# backplate5V_final_rev01.net
KiCad netlist of a schematic drawn in EAGLE
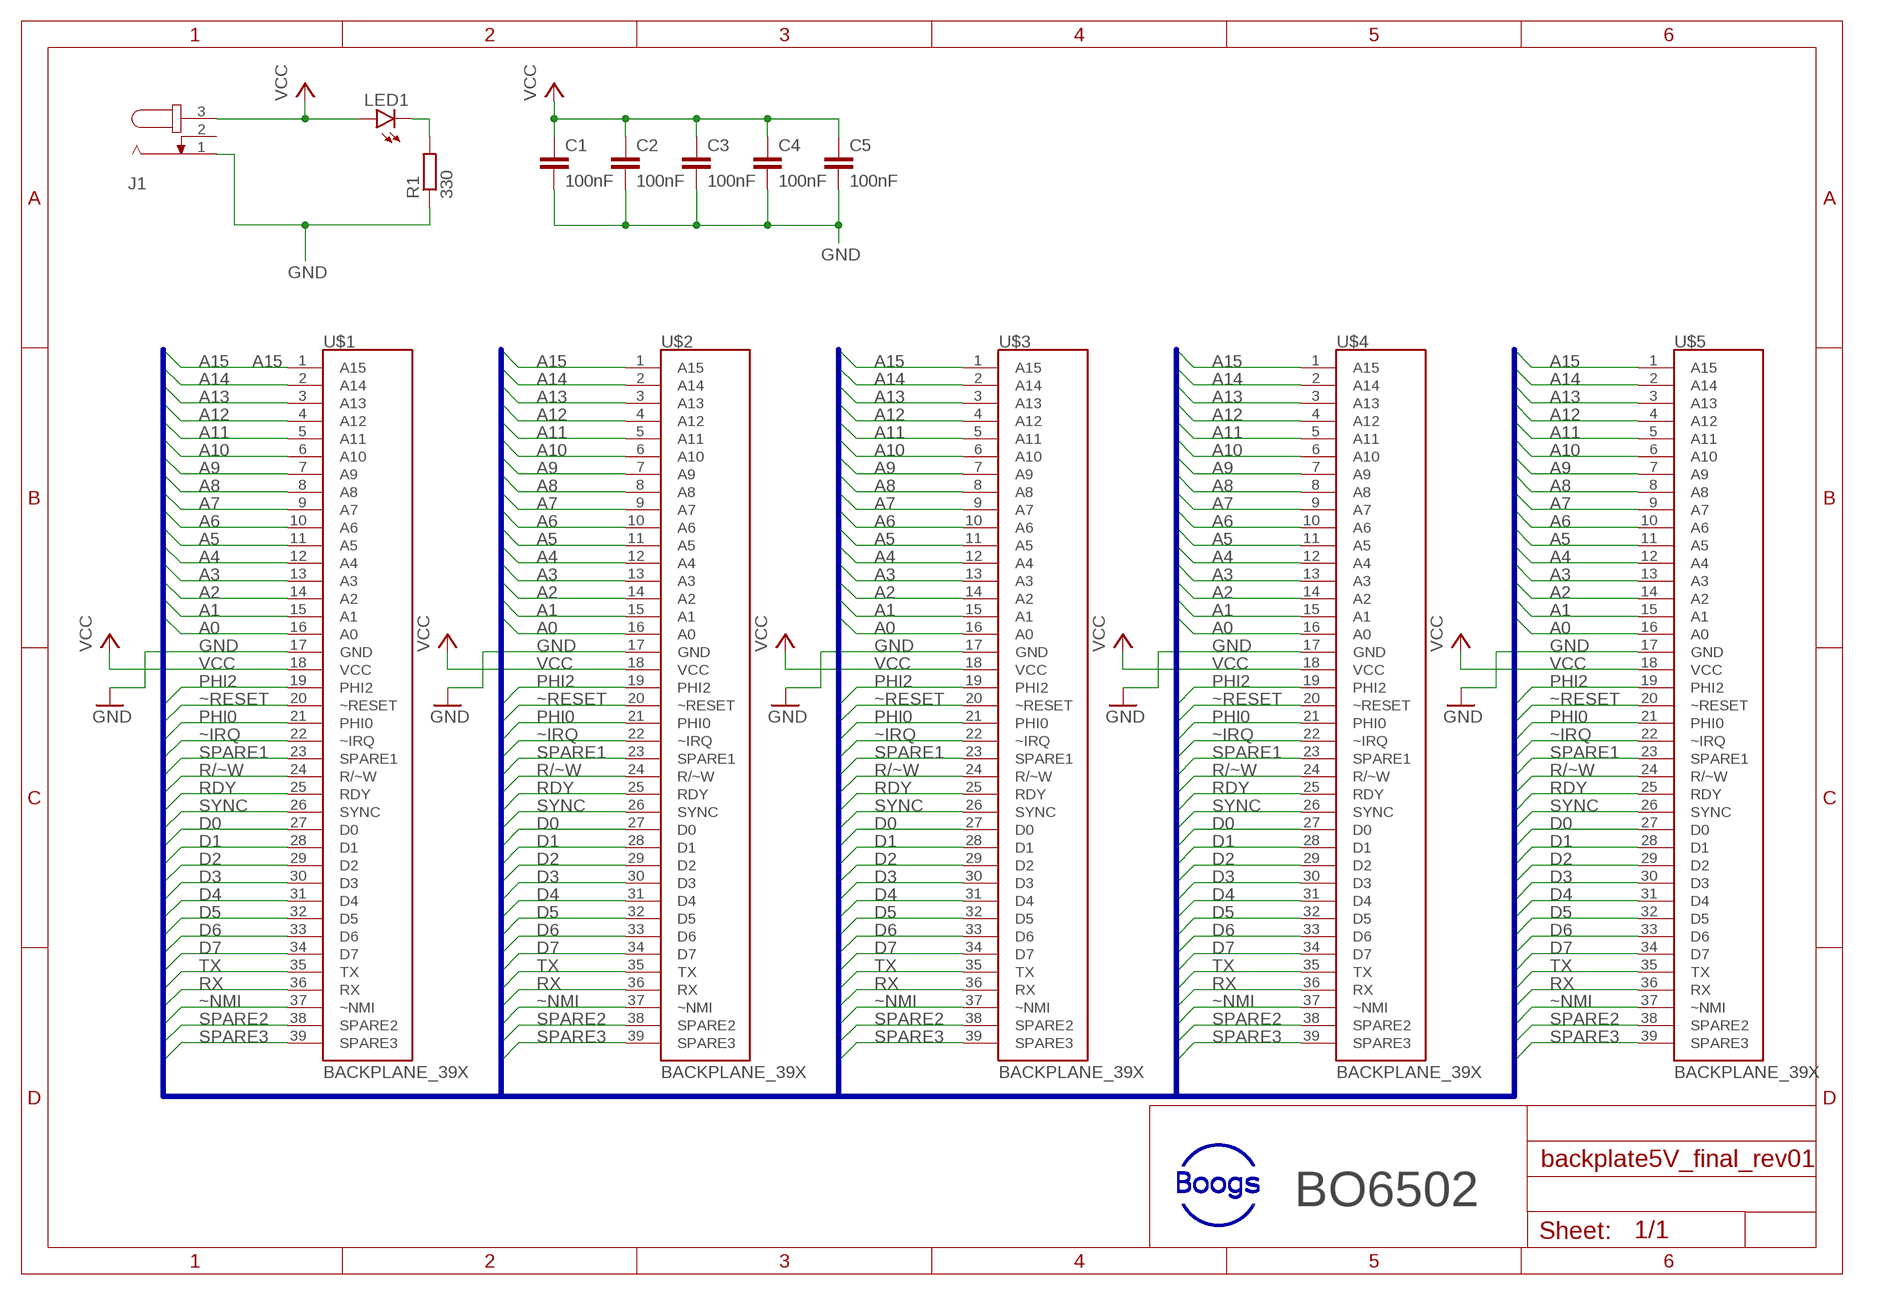
[diagram p0: schematic, sheet 1]

(export (version "E")
  (design (tool "Eeschema 10.0.6"))
  (components
    (comp (ref "C1")
      (value "100nF")
      (footprint "eagle-import:C025-025X050")
      (libsource (lib "eagle-import") (part "C-EU025-025X050"))
    )
    (comp (ref "C2")
      (value "100nF")
      (footprint "eagle-import:C025-025X050")
      (libsource (lib "eagle-import") (part "C-EU025-025X050"))
    )
    (comp (ref "C3")
      (value "100nF")
      (footprint "eagle-import:C025-025X050")
      (libsource (lib "eagle-import") (part "C-EU025-025X050"))
    )
    (comp (ref "C4")
      (value "100nF")
      (footprint "eagle-import:C025-025X050")
      (libsource (lib "eagle-import") (part "C-EU025-025X050"))
    )
    (comp (ref "C5")
      (value "100nF")
      (footprint "eagle-import:C025-025X050")
      (libsource (lib "eagle-import") (part "C-EU025-025X050"))
    )
    (comp (ref "J1")
      (value "JACK-PLUG1")
      (footprint "eagle-import:SPC4078")
      (libsource (lib "eagle-import") (part "JACK-PLUG1"))
    )
    (comp (ref "LED1")
      (value "LED5MM")
      (footprint "eagle-import:LED5MM")
      (libsource (lib "eagle-import") (part "LED5MM"))
    )
    (comp (ref "R1")
      (value "330")
      (footprint "eagle-import:0207_10")
      (libsource (lib "eagle-import") (part "R-EU_0207/10"))
    )
    (comp (ref "U$1")
      (value "BACKPLANE_39X")
      (footprint "eagle-import:BP_39X")
      (fields (field (name "A15") "A15"))
      (libsource (lib "eagle-import") (part "BACKPLANE_39X"))
    )
    (comp (ref "U$2")
      (value "BACKPLANE_39X")
      (footprint "eagle-import:BP_39X")
      (libsource (lib "eagle-import") (part "BACKPLANE_39X"))
    )
    (comp (ref "U$3")
      (value "BACKPLANE_39X")
      (footprint "eagle-import:BP_39X")
      (libsource (lib "eagle-import") (part "BACKPLANE_39X"))
    )
    (comp (ref "U$4")
      (value "BACKPLANE_39X")
      (footprint "eagle-import:BP_39X")
      (libsource (lib "eagle-import") (part "BACKPLANE_39X"))
    )
    (comp (ref "U$5")
      (value "BACKPLANE_39X")
      (footprint "eagle-import:BP_39X")
      (libsource (lib "eagle-import") (part "BACKPLANE_39X"))
    )
  )
  (nets
    (net (code "1") (name "/A0") (class "Default")
      (node (ref "U$1") (pin "16") (pinfunction "A0_16") (pintype "bidirectional"))
      (node (ref "U$2") (pin "16") (pinfunction "A0_16") (pintype "bidirectional"))
      (node (ref "U$3") (pin "16") (pinfunction "A0_16") (pintype "bidirectional"))
      (node (ref "U$4") (pin "16") (pinfunction "A0_16") (pintype "bidirectional"))
      (node (ref "U$5") (pin "16") (pinfunction "A0_16") (pintype "bidirectional"))
    )
    (net (code "2") (name "/A1") (class "Default")
      (node (ref "U$1") (pin "15") (pinfunction "A1_15") (pintype "bidirectional"))
      (node (ref "U$2") (pin "15") (pinfunction "A1_15") (pintype "bidirectional"))
      (node (ref "U$3") (pin "15") (pinfunction "A1_15") (pintype "bidirectional"))
      (node (ref "U$4") (pin "15") (pinfunction "A1_15") (pintype "bidirectional"))
      (node (ref "U$5") (pin "15") (pinfunction "A1_15") (pintype "bidirectional"))
    )
    (net (code "3") (name "/A2") (class "Default")
      (node (ref "U$1") (pin "14") (pinfunction "A2_14") (pintype "bidirectional"))
      (node (ref "U$2") (pin "14") (pinfunction "A2_14") (pintype "bidirectional"))
      (node (ref "U$3") (pin "14") (pinfunction "A2_14") (pintype "bidirectional"))
      (node (ref "U$4") (pin "14") (pinfunction "A2_14") (pintype "bidirectional"))
      (node (ref "U$5") (pin "14") (pinfunction "A2_14") (pintype "bidirectional"))
    )
    (net (code "4") (name "/A3") (class "Default")
      (node (ref "U$1") (pin "13") (pinfunction "A3_13") (pintype "bidirectional"))
      (node (ref "U$2") (pin "13") (pinfunction "A3_13") (pintype "bidirectional"))
      (node (ref "U$3") (pin "13") (pinfunction "A3_13") (pintype "bidirectional"))
      (node (ref "U$4") (pin "13") (pinfunction "A3_13") (pintype "bidirectional"))
      (node (ref "U$5") (pin "13") (pinfunction "A3_13") (pintype "bidirectional"))
    )
    (net (code "5") (name "/A4") (class "Default")
      (node (ref "U$1") (pin "12") (pinfunction "A4_12") (pintype "bidirectional"))
      (node (ref "U$2") (pin "12") (pinfunction "A4_12") (pintype "bidirectional"))
      (node (ref "U$3") (pin "12") (pinfunction "A4_12") (pintype "bidirectional"))
      (node (ref "U$4") (pin "12") (pinfunction "A4_12") (pintype "bidirectional"))
      (node (ref "U$5") (pin "12") (pinfunction "A4_12") (pintype "bidirectional"))
    )
    (net (code "6") (name "/A5") (class "Default")
      (node (ref "U$1") (pin "11") (pinfunction "A5_11") (pintype "bidirectional"))
      (node (ref "U$2") (pin "11") (pinfunction "A5_11") (pintype "bidirectional"))
      (node (ref "U$3") (pin "11") (pinfunction "A5_11") (pintype "bidirectional"))
      (node (ref "U$4") (pin "11") (pinfunction "A5_11") (pintype "bidirectional"))
      (node (ref "U$5") (pin "11") (pinfunction "A5_11") (pintype "bidirectional"))
    )
    (net (code "7") (name "/A6") (class "Default")
      (node (ref "U$1") (pin "10") (pinfunction "A6_10") (pintype "bidirectional"))
      (node (ref "U$2") (pin "10") (pinfunction "A6_10") (pintype "bidirectional"))
      (node (ref "U$3") (pin "10") (pinfunction "A6_10") (pintype "bidirectional"))
      (node (ref "U$4") (pin "10") (pinfunction "A6_10") (pintype "bidirectional"))
      (node (ref "U$5") (pin "10") (pinfunction "A6_10") (pintype "bidirectional"))
    )
    (net (code "8") (name "/A7") (class "Default")
      (node (ref "U$1") (pin "9") (pinfunction "A7_9") (pintype "bidirectional"))
      (node (ref "U$2") (pin "9") (pinfunction "A7_9") (pintype "bidirectional"))
      (node (ref "U$3") (pin "9") (pinfunction "A7_9") (pintype "bidirectional"))
      (node (ref "U$4") (pin "9") (pinfunction "A7_9") (pintype "bidirectional"))
      (node (ref "U$5") (pin "9") (pinfunction "A7_9") (pintype "bidirectional"))
    )
    (net (code "9") (name "/A8") (class "Default")
      (node (ref "U$1") (pin "8") (pinfunction "A8_8") (pintype "bidirectional"))
      (node (ref "U$2") (pin "8") (pinfunction "A8_8") (pintype "bidirectional"))
      (node (ref "U$3") (pin "8") (pinfunction "A8_8") (pintype "bidirectional"))
      (node (ref "U$4") (pin "8") (pinfunction "A8_8") (pintype "bidirectional"))
      (node (ref "U$5") (pin "8") (pinfunction "A8_8") (pintype "bidirectional"))
    )
    (net (code "10") (name "/A9") (class "Default")
      (node (ref "U$1") (pin "7") (pinfunction "A9_7") (pintype "bidirectional"))
      (node (ref "U$2") (pin "7") (pinfunction "A9_7") (pintype "bidirectional"))
      (node (ref "U$3") (pin "7") (pinfunction "A9_7") (pintype "bidirectional"))
      (node (ref "U$4") (pin "7") (pinfunction "A9_7") (pintype "bidirectional"))
      (node (ref "U$5") (pin "7") (pinfunction "A9_7") (pintype "bidirectional"))
    )
    (net (code "11") (name "/A10") (class "Default")
      (node (ref "U$1") (pin "6") (pinfunction "A10_6") (pintype "bidirectional"))
      (node (ref "U$2") (pin "6") (pinfunction "A10_6") (pintype "bidirectional"))
      (node (ref "U$3") (pin "6") (pinfunction "A10_6") (pintype "bidirectional"))
      (node (ref "U$4") (pin "6") (pinfunction "A10_6") (pintype "bidirectional"))
      (node (ref "U$5") (pin "6") (pinfunction "A10_6") (pintype "bidirectional"))
    )
    (net (code "12") (name "/A11") (class "Default")
      (node (ref "U$1") (pin "5") (pinfunction "A11_5") (pintype "bidirectional"))
      (node (ref "U$2") (pin "5") (pinfunction "A11_5") (pintype "bidirectional"))
      (node (ref "U$3") (pin "5") (pinfunction "A11_5") (pintype "bidirectional"))
      (node (ref "U$4") (pin "5") (pinfunction "A11_5") (pintype "bidirectional"))
      (node (ref "U$5") (pin "5") (pinfunction "A11_5") (pintype "bidirectional"))
    )
    (net (code "13") (name "/A12") (class "Default")
      (node (ref "U$1") (pin "4") (pinfunction "A12_4") (pintype "bidirectional"))
      (node (ref "U$2") (pin "4") (pinfunction "A12_4") (pintype "bidirectional"))
      (node (ref "U$3") (pin "4") (pinfunction "A12_4") (pintype "bidirectional"))
      (node (ref "U$4") (pin "4") (pinfunction "A12_4") (pintype "bidirectional"))
      (node (ref "U$5") (pin "4") (pinfunction "A12_4") (pintype "bidirectional"))
    )
    (net (code "14") (name "/A13") (class "Default")
      (node (ref "U$1") (pin "3") (pinfunction "A13_3") (pintype "bidirectional"))
      (node (ref "U$2") (pin "3") (pinfunction "A13_3") (pintype "bidirectional"))
      (node (ref "U$3") (pin "3") (pinfunction "A13_3") (pintype "bidirectional"))
      (node (ref "U$4") (pin "3") (pinfunction "A13_3") (pintype "bidirectional"))
      (node (ref "U$5") (pin "3") (pinfunction "A13_3") (pintype "bidirectional"))
    )
    (net (code "15") (name "/A14") (class "Default")
      (node (ref "U$1") (pin "2") (pinfunction "A14_2") (pintype "bidirectional"))
      (node (ref "U$2") (pin "2") (pinfunction "A14_2") (pintype "bidirectional"))
      (node (ref "U$3") (pin "2") (pinfunction "A14_2") (pintype "bidirectional"))
      (node (ref "U$4") (pin "2") (pinfunction "A14_2") (pintype "bidirectional"))
      (node (ref "U$5") (pin "2") (pinfunction "A14_2") (pintype "bidirectional"))
    )
    (net (code "16") (name "/A15") (class "Default")
      (node (ref "U$1") (pin "1") (pinfunction "A15_1") (pintype "bidirectional"))
      (node (ref "U$2") (pin "1") (pinfunction "A15_1") (pintype "bidirectional"))
      (node (ref "U$3") (pin "1") (pinfunction "A15_1") (pintype "bidirectional"))
      (node (ref "U$4") (pin "1") (pinfunction "A15_1") (pintype "bidirectional"))
      (node (ref "U$5") (pin "1") (pinfunction "A15_1") (pintype "bidirectional"))
    )
    (net (code "17") (name "/D0") (class "Default")
      (node (ref "U$1") (pin "27") (pinfunction "D0_27") (pintype "bidirectional"))
      (node (ref "U$2") (pin "27") (pinfunction "D0_27") (pintype "bidirectional"))
      (node (ref "U$3") (pin "27") (pinfunction "D0_27") (pintype "bidirectional"))
      (node (ref "U$4") (pin "27") (pinfunction "D0_27") (pintype "bidirectional"))
      (node (ref "U$5") (pin "27") (pinfunction "D0_27") (pintype "bidirectional"))
    )
    (net (code "18") (name "/D1") (class "Default")
      (node (ref "U$1") (pin "28") (pinfunction "D1_28") (pintype "bidirectional"))
      (node (ref "U$2") (pin "28") (pinfunction "D1_28") (pintype "bidirectional"))
      (node (ref "U$3") (pin "28") (pinfunction "D1_28") (pintype "bidirectional"))
      (node (ref "U$4") (pin "28") (pinfunction "D1_28") (pintype "bidirectional"))
      (node (ref "U$5") (pin "28") (pinfunction "D1_28") (pintype "bidirectional"))
    )
    (net (code "19") (name "/D2") (class "Default")
      (node (ref "U$1") (pin "29") (pinfunction "D2_29") (pintype "bidirectional"))
      (node (ref "U$2") (pin "29") (pinfunction "D2_29") (pintype "bidirectional"))
      (node (ref "U$3") (pin "29") (pinfunction "D2_29") (pintype "bidirectional"))
      (node (ref "U$4") (pin "29") (pinfunction "D2_29") (pintype "bidirectional"))
      (node (ref "U$5") (pin "29") (pinfunction "D2_29") (pintype "bidirectional"))
    )
    (net (code "20") (name "/D3") (class "Default")
      (node (ref "U$1") (pin "30") (pinfunction "D3_30") (pintype "bidirectional"))
      (node (ref "U$2") (pin "30") (pinfunction "D3_30") (pintype "bidirectional"))
      (node (ref "U$3") (pin "30") (pinfunction "D3_30") (pintype "bidirectional"))
      (node (ref "U$4") (pin "30") (pinfunction "D3_30") (pintype "bidirectional"))
      (node (ref "U$5") (pin "30") (pinfunction "D3_30") (pintype "bidirectional"))
    )
    (net (code "21") (name "/D4") (class "Default")
      (node (ref "U$1") (pin "31") (pinfunction "D4_31") (pintype "bidirectional"))
      (node (ref "U$2") (pin "31") (pinfunction "D4_31") (pintype "bidirectional"))
      (node (ref "U$3") (pin "31") (pinfunction "D4_31") (pintype "bidirectional"))
      (node (ref "U$4") (pin "31") (pinfunction "D4_31") (pintype "bidirectional"))
      (node (ref "U$5") (pin "31") (pinfunction "D4_31") (pintype "bidirectional"))
    )
    (net (code "22") (name "/D5") (class "Default")
      (node (ref "U$1") (pin "32") (pinfunction "D5_32") (pintype "bidirectional"))
      (node (ref "U$2") (pin "32") (pinfunction "D5_32") (pintype "bidirectional"))
      (node (ref "U$3") (pin "32") (pinfunction "D5_32") (pintype "bidirectional"))
      (node (ref "U$4") (pin "32") (pinfunction "D5_32") (pintype "bidirectional"))
      (node (ref "U$5") (pin "32") (pinfunction "D5_32") (pintype "bidirectional"))
    )
    (net (code "23") (name "/D6") (class "Default")
      (node (ref "U$1") (pin "33") (pinfunction "D6_33") (pintype "bidirectional"))
      (node (ref "U$2") (pin "33") (pinfunction "D6_33") (pintype "bidirectional"))
      (node (ref "U$3") (pin "33") (pinfunction "D6_33") (pintype "bidirectional"))
      (node (ref "U$4") (pin "33") (pinfunction "D6_33") (pintype "bidirectional"))
      (node (ref "U$5") (pin "33") (pinfunction "D6_33") (pintype "bidirectional"))
    )
    (net (code "24") (name "/D7") (class "Default")
      (node (ref "U$1") (pin "34") (pinfunction "D7_34") (pintype "bidirectional"))
      (node (ref "U$2") (pin "34") (pinfunction "D7_34") (pintype "bidirectional"))
      (node (ref "U$3") (pin "34") (pinfunction "D7_34") (pintype "bidirectional"))
      (node (ref "U$4") (pin "34") (pinfunction "D7_34") (pintype "bidirectional"))
      (node (ref "U$5") (pin "34") (pinfunction "D7_34") (pintype "bidirectional"))
    )
    (net (code "25") (name "/PHI0") (class "Default")
      (node (ref "U$1") (pin "21") (pinfunction "PHI0_21") (pintype "bidirectional"))
      (node (ref "U$2") (pin "21") (pinfunction "PHI0_21") (pintype "bidirectional"))
      (node (ref "U$3") (pin "21") (pinfunction "PHI0_21") (pintype "bidirectional"))
      (node (ref "U$4") (pin "21") (pinfunction "PHI0_21") (pintype "bidirectional"))
      (node (ref "U$5") (pin "21") (pinfunction "PHI0_21") (pintype "bidirectional"))
    )
    (net (code "26") (name "/PHI2") (class "Default")
      (node (ref "U$1") (pin "19") (pinfunction "PHI2_19") (pintype "bidirectional"))
      (node (ref "U$2") (pin "19") (pinfunction "PHI2_19") (pintype "bidirectional"))
      (node (ref "U$3") (pin "19") (pinfunction "PHI2_19") (pintype "bidirectional"))
      (node (ref "U$4") (pin "19") (pinfunction "PHI2_19") (pintype "bidirectional"))
      (node (ref "U$5") (pin "19") (pinfunction "PHI2_19") (pintype "bidirectional"))
    )
    (net (code "27") (name "/RDY") (class "Default")
      (node (ref "U$1") (pin "25") (pinfunction "RDY_25") (pintype "bidirectional"))
      (node (ref "U$2") (pin "25") (pinfunction "RDY_25") (pintype "bidirectional"))
      (node (ref "U$3") (pin "25") (pinfunction "RDY_25") (pintype "bidirectional"))
      (node (ref "U$4") (pin "25") (pinfunction "RDY_25") (pintype "bidirectional"))
      (node (ref "U$5") (pin "25") (pinfunction "RDY_25") (pintype "bidirectional"))
    )
    (net (code "28") (name "/RX") (class "Default")
      (node (ref "U$1") (pin "36") (pinfunction "RX_36") (pintype "bidirectional"))
      (node (ref "U$2") (pin "36") (pinfunction "RX_36") (pintype "bidirectional"))
      (node (ref "U$3") (pin "36") (pinfunction "RX_36") (pintype "bidirectional"))
      (node (ref "U$4") (pin "36") (pinfunction "RX_36") (pintype "bidirectional"))
      (node (ref "U$5") (pin "36") (pinfunction "RX_36") (pintype "bidirectional"))
    )
    (net (code "29") (name "/R{slash}~{W}") (class "Default")
      (node (ref "U$1") (pin "24") (pinfunction "R/~{W}_24") (pintype "bidirectional"))
      (node (ref "U$2") (pin "24") (pinfunction "R/~{W}_24") (pintype "bidirectional"))
      (node (ref "U$3") (pin "24") (pinfunction "R/~{W}_24") (pintype "bidirectional"))
      (node (ref "U$4") (pin "24") (pinfunction "R/~{W}_24") (pintype "bidirectional"))
      (node (ref "U$5") (pin "24") (pinfunction "R/~{W}_24") (pintype "bidirectional"))
    )
    (net (code "30") (name "/SPARE1") (class "Default")
      (node (ref "U$1") (pin "23") (pinfunction "SPARE1_23") (pintype "bidirectional"))
      (node (ref "U$2") (pin "23") (pinfunction "SPARE1_23") (pintype "bidirectional"))
      (node (ref "U$3") (pin "23") (pinfunction "SPARE1_23") (pintype "bidirectional"))
      (node (ref "U$4") (pin "23") (pinfunction "SPARE1_23") (pintype "bidirectional"))
      (node (ref "U$5") (pin "23") (pinfunction "SPARE1_23") (pintype "bidirectional"))
    )
    (net (code "31") (name "/SPARE2") (class "Default")
      (node (ref "U$1") (pin "38") (pinfunction "SPARE2_38") (pintype "bidirectional"))
      (node (ref "U$2") (pin "38") (pinfunction "SPARE2_38") (pintype "bidirectional"))
      (node (ref "U$3") (pin "38") (pinfunction "SPARE2_38") (pintype "bidirectional"))
      (node (ref "U$4") (pin "38") (pinfunction "SPARE2_38") (pintype "bidirectional"))
      (node (ref "U$5") (pin "38") (pinfunction "SPARE2_38") (pintype "bidirectional"))
    )
    (net (code "32") (name "/SPARE3") (class "Default")
      (node (ref "U$1") (pin "39") (pinfunction "SPARE3_39") (pintype "bidirectional"))
      (node (ref "U$2") (pin "39") (pinfunction "SPARE3_39") (pintype "bidirectional"))
      (node (ref "U$3") (pin "39") (pinfunction "SPARE3_39") (pintype "bidirectional"))
      (node (ref "U$4") (pin "39") (pinfunction "SPARE3_39") (pintype "bidirectional"))
      (node (ref "U$5") (pin "39") (pinfunction "SPARE3_39") (pintype "bidirectional"))
    )
    (net (code "33") (name "/SYNC") (class "Default")
      (node (ref "U$1") (pin "26") (pinfunction "SYNC_26") (pintype "bidirectional"))
      (node (ref "U$2") (pin "26") (pinfunction "SYNC_26") (pintype "bidirectional"))
      (node (ref "U$3") (pin "26") (pinfunction "SYNC_26") (pintype "bidirectional"))
      (node (ref "U$4") (pin "26") (pinfunction "SYNC_26") (pintype "bidirectional"))
      (node (ref "U$5") (pin "26") (pinfunction "SYNC_26") (pintype "bidirectional"))
    )
    (net (code "34") (name "/TX") (class "Default")
      (node (ref "U$1") (pin "35") (pinfunction "TX_35") (pintype "bidirectional"))
      (node (ref "U$2") (pin "35") (pinfunction "TX_35") (pintype "bidirectional"))
      (node (ref "U$3") (pin "35") (pinfunction "TX_35") (pintype "bidirectional"))
      (node (ref "U$4") (pin "35") (pinfunction "TX_35") (pintype "bidirectional"))
      (node (ref "U$5") (pin "35") (pinfunction "TX_35") (pintype "bidirectional"))
    )
    (net (code "35") (name "/~{IRQ}") (class "Default")
      (node (ref "U$1") (pin "22") (pinfunction "~{IRQ}_22") (pintype "bidirectional"))
      (node (ref "U$2") (pin "22") (pinfunction "~{IRQ}_22") (pintype "bidirectional"))
      (node (ref "U$3") (pin "22") (pinfunction "~{IRQ}_22") (pintype "bidirectional"))
      (node (ref "U$4") (pin "22") (pinfunction "~{IRQ}_22") (pintype "bidirectional"))
      (node (ref "U$5") (pin "22") (pinfunction "~{IRQ}_22") (pintype "bidirectional"))
    )
    (net (code "36") (name "/~{NMI}") (class "Default")
      (node (ref "U$1") (pin "37") (pinfunction "~{NMI}_37") (pintype "bidirectional"))
      (node (ref "U$2") (pin "37") (pinfunction "~{NMI}_37") (pintype "bidirectional"))
      (node (ref "U$3") (pin "37") (pinfunction "~{NMI}_37") (pintype "bidirectional"))
      (node (ref "U$4") (pin "37") (pinfunction "~{NMI}_37") (pintype "bidirectional"))
      (node (ref "U$5") (pin "37") (pinfunction "~{NMI}_37") (pintype "bidirectional"))
    )
    (net (code "37") (name "/~{RESET}") (class "Default")
      (node (ref "U$1") (pin "20") (pinfunction "~{RESET}_20") (pintype "bidirectional"))
      (node (ref "U$2") (pin "20") (pinfunction "~{RESET}_20") (pintype "bidirectional"))
      (node (ref "U$3") (pin "20") (pinfunction "~{RESET}_20") (pintype "bidirectional"))
      (node (ref "U$4") (pin "20") (pinfunction "~{RESET}_20") (pintype "bidirectional"))
      (node (ref "U$5") (pin "20") (pinfunction "~{RESET}_20") (pintype "bidirectional"))
    )
    (net (code "38") (name "GND") (class "Default")
      (node (ref "C1") (pin "2") (pinfunction "2_2") (pintype "passive"))
      (node (ref "C2") (pin "2") (pinfunction "2_2") (pintype "passive"))
      (node (ref "C3") (pin "2") (pinfunction "2_2") (pintype "passive"))
      (node (ref "C4") (pin "2") (pinfunction "2_2") (pintype "passive"))
      (node (ref "C5") (pin "2") (pinfunction "2_2") (pintype "passive"))
      (node (ref "J1") (pin "1") (pinfunction "1_1") (pintype "passive"))
      (node (ref "R1") (pin "1") (pinfunction "1_1") (pintype "passive"))
      (node (ref "U$1") (pin "17") (pinfunction "GND_17") (pintype "bidirectional"))
      (node (ref "U$2") (pin "17") (pinfunction "GND_17") (pintype "bidirectional"))
      (node (ref "U$3") (pin "17") (pinfunction "GND_17") (pintype "bidirectional"))
      (node (ref "U$4") (pin "17") (pinfunction "GND_17") (pintype "bidirectional"))
      (node (ref "U$5") (pin "17") (pinfunction "GND_17") (pintype "bidirectional"))
    )
    (net (code "39") (name "Net-(LED1-C)") (class "Default")
      (node (ref "LED1") (pin "K") (pinfunction "C_K") (pintype "passive"))
      (node (ref "R1") (pin "2") (pinfunction "2_2") (pintype "passive"))
    )
    (net (code "40") (name "VCC") (class "Default")
      (node (ref "C1") (pin "1") (pinfunction "1_1") (pintype "passive"))
      (node (ref "C2") (pin "1") (pinfunction "1_1") (pintype "passive"))
      (node (ref "C3") (pin "1") (pinfunction "1_1") (pintype "passive"))
      (node (ref "C4") (pin "1") (pinfunction "1_1") (pintype "passive"))
      (node (ref "C5") (pin "1") (pinfunction "1_1") (pintype "passive"))
      (node (ref "J1") (pin "3") (pinfunction "3_3") (pintype "passive"))
      (node (ref "LED1") (pin "A") (pinfunction "A_A") (pintype "passive"))
      (node (ref "U$1") (pin "18") (pinfunction "VCC_18") (pintype "bidirectional"))
      (node (ref "U$2") (pin "18") (pinfunction "VCC_18") (pintype "bidirectional"))
      (node (ref "U$3") (pin "18") (pinfunction "VCC_18") (pintype "bidirectional"))
      (node (ref "U$4") (pin "18") (pinfunction "VCC_18") (pintype "bidirectional"))
      (node (ref "U$5") (pin "18") (pinfunction "VCC_18") (pintype "bidirectional"))
    )
    (net (code "41") (name "unconnected-(J1-Pad2)") (class "Default")
      (node (ref "J1") (pin "2") (pinfunction "2_2") (pintype "passive"))
    )
  )
)
